# Rotary_Encoder.net
KiCad netlist of a schematic drawn in Altium Designer
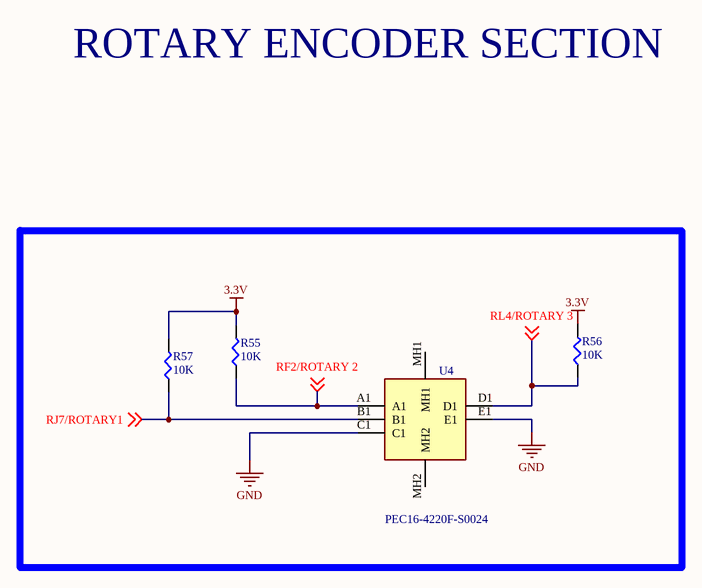
[diagram p0: Rotary Encoder.SchDoc]

(export (version "E")
  (design (tool "Eeschema 10.0.6"))
  (components
    (comp (ref "R55")
      (value "10K")
      (footprint "SMD-0805-RES")
      (description "RES SMD 1K OHM 1% 1/8W 0805")
      (fields
        (field (name "PART NUMBER") "ERJ-6ENF1001V")
        (field (name "DIGI-KEY PART NUMBER") "P1.00KCCT-ND")
      )
      (libsource (lib "Panasonic_ERJ_0805") (part "ERJ-6ENF1001V"))
    )
    (comp (ref "R56")
      (value "10K")
      (footprint "SMD-0805-RES")
      (description "RES SMD 1K OHM 1% 1/8W 0805")
      (fields
        (field (name "PART NUMBER") "ERJ-6ENF1001V")
        (field (name "DIGI-KEY PART NUMBER") "P1.00KCCT-ND")
      )
      (libsource (lib "Panasonic_ERJ_0805") (part "ERJ-6ENF1001V"))
    )
    (comp (ref "R57")
      (value "10K")
      (footprint "SMD-0805-RES")
      (description "RES SMD 1K OHM 1% 1/8W 0805")
      (fields
        (field (name "PART NUMBER") "ERJ-6ENF1001V")
        (field (name "DIGI-KEY PART NUMBER") "P1.00KCCT-ND")
      )
      (libsource (lib "Panasonic_ERJ_0805") (part "ERJ-6ENF1001V"))
    )
    (comp (ref "U4")
      (value "PEC16-4220F-S0024")
      (footprint "SamacSys:PEC164120FS0012")
      (description "Undefined or Miscellaneous")
      (fields (field (name "MOUSER PART NUMBER") "652-PEC16-4220FS0024"))
      (libsource (lib "SamacSys") (part "PEC16-4220F-S0024"))
    )
  )
  (nets
    (net (code "1") (name "3.3V") (class "Default")
      (node (ref "R55") (pin "2") (pinfunction "2_2") (pintype "passive"))
      (node (ref "R56") (pin "2") (pinfunction "2_2") (pintype "passive"))
      (node (ref "R57") (pin "2") (pinfunction "2_2") (pintype "passive"))
    )
    (net (code "2") (name "GND") (class "Default")
      (node (ref "U4") (pin "C1") (pinfunction "C1_C1") (pintype "passive"))
      (node (ref "U4") (pin "E1") (pinfunction "E1_E1") (pintype "passive"))
    )
    (net (code "3") (name "RF2{slash}ROTARY 2") (class "Default")
      (node (ref "R55") (pin "1") (pinfunction "1_1") (pintype "passive"))
      (node (ref "U4") (pin "A1") (pinfunction "A1_A1") (pintype "passive"))
    )
    (net (code "4") (name "RJ7{slash}ROTARY1") (class "Default")
      (node (ref "R57") (pin "1") (pinfunction "1_1") (pintype "passive"))
      (node (ref "U4") (pin "B1") (pinfunction "B1_B1") (pintype "passive"))
    )
    (net (code "5") (name "RL4{slash}ROTARY 3") (class "Default")
      (node (ref "R56") (pin "1") (pinfunction "1_1") (pintype "passive"))
      (node (ref "U4") (pin "D1") (pinfunction "D1_D1") (pintype "passive"))
    )
    (net (code "6") (name "unconnected-(U4-PadMH1)") (class "Default")
      (node (ref "U4") (pin "MH1") (pinfunction "MH1_MH1") (pintype "passive"))
    )
    (net (code "7") (name "unconnected-(U4-PadMH2)") (class "Default")
      (node (ref "U4") (pin "MH2") (pinfunction "MH2_MH2") (pintype "passive"))
    )
  )
)
